# BM_Tone_Stack.net
KiCad netlist of a schematic drawn in Altium Designer
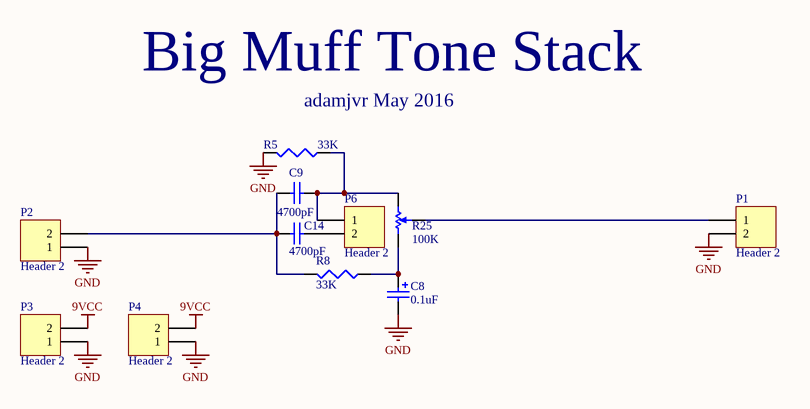
[diagram p0: BM Tone Stack.SchDoc]

(export (version "E")
  (design (tool "Eeschema 10.0.6"))
  (components
    (comp (ref "C8")
      (value "0.1uF")
      (footprint "5X12.5mmCAP")
      (description "CAP ALUM 0.1UF 20% 100V RADIAL")
      (fields
        (field (name "MFR") "Nichicon")
        (field (name "TOLERANCE") "20%")
        (field (name "DESIGNER") "Adam Vadala-Roth")
      )
      (libsource (lib "AudioPartLib") (part "UFG2A0R1MDM1TD"))
    )
    (comp (ref "C9")
      (value "4700pF")
      (footprint "VY2472M49Y5US63V7")
      (fields
        (field (name "MFR") "Vishay-BC-Components")
        (field (name "TOLERANCE") "20%")
        (field (name "VOLTAGE") "440VAC")
        (field (name "DESIGNER") "Adam Vadala-Roth")
      )
      (libsource (lib "AudioPartLib") (part "VY2472M49Y5US63V7"))
    )
    (comp (ref "C14")
      (value "4700pF")
      (footprint "VY2472M49Y5US63V7")
      (fields
        (field (name "MFR") "Vishay-BC-Components")
        (field (name "TOLERANCE") "20%")
        (field (name "VOLTAGE") "440VAC")
        (field (name "DESIGNER") "Adam Vadala-Roth")
      )
      (libsource (lib "AudioPartLib") (part "VY2472M49Y5US63V7"))
    )
    (comp (ref "P1")
      (value "Header 2")
      (footprint "HDR1X2")
      (description "Header, 2-Pin")
      (fields (field (name "PUBLISHER") "Altium Limited"))
      (libsource (lib "") (part "Header 2_1"))
    )
    (comp (ref "P2")
      (value "Header 2")
      (footprint "HDR1X2")
      (description "Header, 2-Pin")
      (fields (field (name "PUBLISHER") "Altium Limited"))
      (libsource (lib "Miscellaneous Connectors") (part "Header 2"))
    )
    (comp (ref "P3")
      (value "Header 2")
      (footprint "HDR1X2")
      (description "Header, 2-Pin")
      (fields (field (name "PUBLISHER") "Altium Limited"))
      (libsource (lib "Miscellaneous Connectors") (part "Header 2"))
    )
    (comp (ref "P4")
      (value "Header 2")
      (footprint "HDR1X2")
      (description "Header, 2-Pin")
      (fields (field (name "PUBLISHER") "Altium Limited"))
      (libsource (lib "Miscellaneous Connectors") (part "Header 2"))
    )
    (comp (ref "P6")
      (value "Header 2")
      (footprint "HDR1X2")
      (description "Header, 2-Pin")
      (fields (field (name "PUBLISHER") "Altium Limited"))
      (libsource (lib "") (part "Header 2_1"))
    )
    (comp (ref "R5")
      (value "33K")
      (footprint "R0805")
      (description "RES SMD 33K OHM 1% 1/8W 0805")
      (fields
        (field (name "MFR") "Panasonic-Electronic-Components")
        (field (name "TOLERANCE") "1%")
        (field (name "DESIGNER") "Adam Vadala-Roth")
      )
      (libsource (lib "AudioPartLib") (part "ERJ-6ENF3302V"))
    )
    (comp (ref "R8")
      (value "33K")
      (footprint "R0805")
      (description "RES SMD 33K OHM 1% 1/8W 0805")
      (fields
        (field (name "MFR") "Panasonic-Electronic-Components")
        (field (name "TOLERANCE") "1%")
        (field (name "DESIGNER") "Adam Vadala-Roth")
      )
      (libsource (lib "AudioPartLib") (part "ERJ-6ENF3302V"))
    )
    (comp (ref "R25")
      (value "100K")
      (footprint "BOURNS_PTD90SERIES_POT")
      (description "POT 100K OHM 1/20W CARBON LINEAR")
      (fields
        (field (name "MFR") "Bourns Inc.")
        (field (name "TOLERANCE") "20%")
        (field (name "DESIGNER") "Adam Vadala-Roth")
      )
      (libsource (lib "AudioPartLib") (part "PTD901-2015K-B104"))
    )
  )
  (nets
    (net (code "1") (name "9VCC") (class "Default")
      (node (ref "P3") (pin "2") (pinfunction "2_2") (pintype "passive"))
      (node (ref "P4") (pin "2") (pinfunction "2_2") (pintype "passive"))
    )
    (net (code "2") (name "GND") (class "Default")
      (node (ref "C8") (pin "2") (pinfunction "2_2") (pintype "passive"))
      (node (ref "P1") (pin "2") (pinfunction "2_2") (pintype "passive"))
      (node (ref "P2") (pin "1") (pinfunction "1_1") (pintype "passive"))
      (node (ref "P3") (pin "1") (pinfunction "1_1") (pintype "passive"))
      (node (ref "P4") (pin "1") (pinfunction "1_1") (pintype "passive"))
      (node (ref "R5") (pin "2") (pinfunction "2_2") (pintype "passive"))
    )
    (net (code "3") (name "Net-(C8-Pad1)") (class "Default")
      (node (ref "C8") (pin "1") (pinfunction "1_1") (pintype "passive"))
      (node (ref "R25") (pin "3") (pinfunction "3_3") (pintype "passive"))
      (node (ref "R8") (pin "1") (pinfunction "1_1") (pintype "passive"))
    )
    (net (code "4") (name "Net-(C9-Pad1)") (class "Default")
      (node (ref "C9") (pin "1") (pinfunction "1_1") (pintype "passive"))
      (node (ref "P6") (pin "1") (pinfunction "1_1") (pintype "passive"))
      (node (ref "R25") (pin "1") (pinfunction "1_1") (pintype "passive"))
      (node (ref "R5") (pin "1") (pinfunction "1_1") (pintype "passive"))
    )
    (net (code "5") (name "Net-(C14-Pad1)") (class "Default")
      (node (ref "C14") (pin "1") (pinfunction "1_1") (pintype "passive"))
      (node (ref "P6") (pin "2") (pinfunction "2_2") (pintype "passive"))
    )
    (net (code "6") (name "Net-(C14-Pad2)") (class "Default")
      (node (ref "C14") (pin "2") (pinfunction "2_2") (pintype "passive"))
      (node (ref "C9") (pin "2") (pinfunction "2_2") (pintype "passive"))
      (node (ref "P2") (pin "2") (pinfunction "2_2") (pintype "passive"))
      (node (ref "R8") (pin "2") (pinfunction "2_2") (pintype "passive"))
    )
    (net (code "7") (name "Net-(P1-Pad1)") (class "Default")
      (node (ref "P1") (pin "1") (pinfunction "1_1") (pintype "passive"))
      (node (ref "R25") (pin "2") (pinfunction "2_2") (pintype "passive"))
    )
  )
)
